# ir_smd.net
KiCad netlist of a schematic drawn in EAGLE
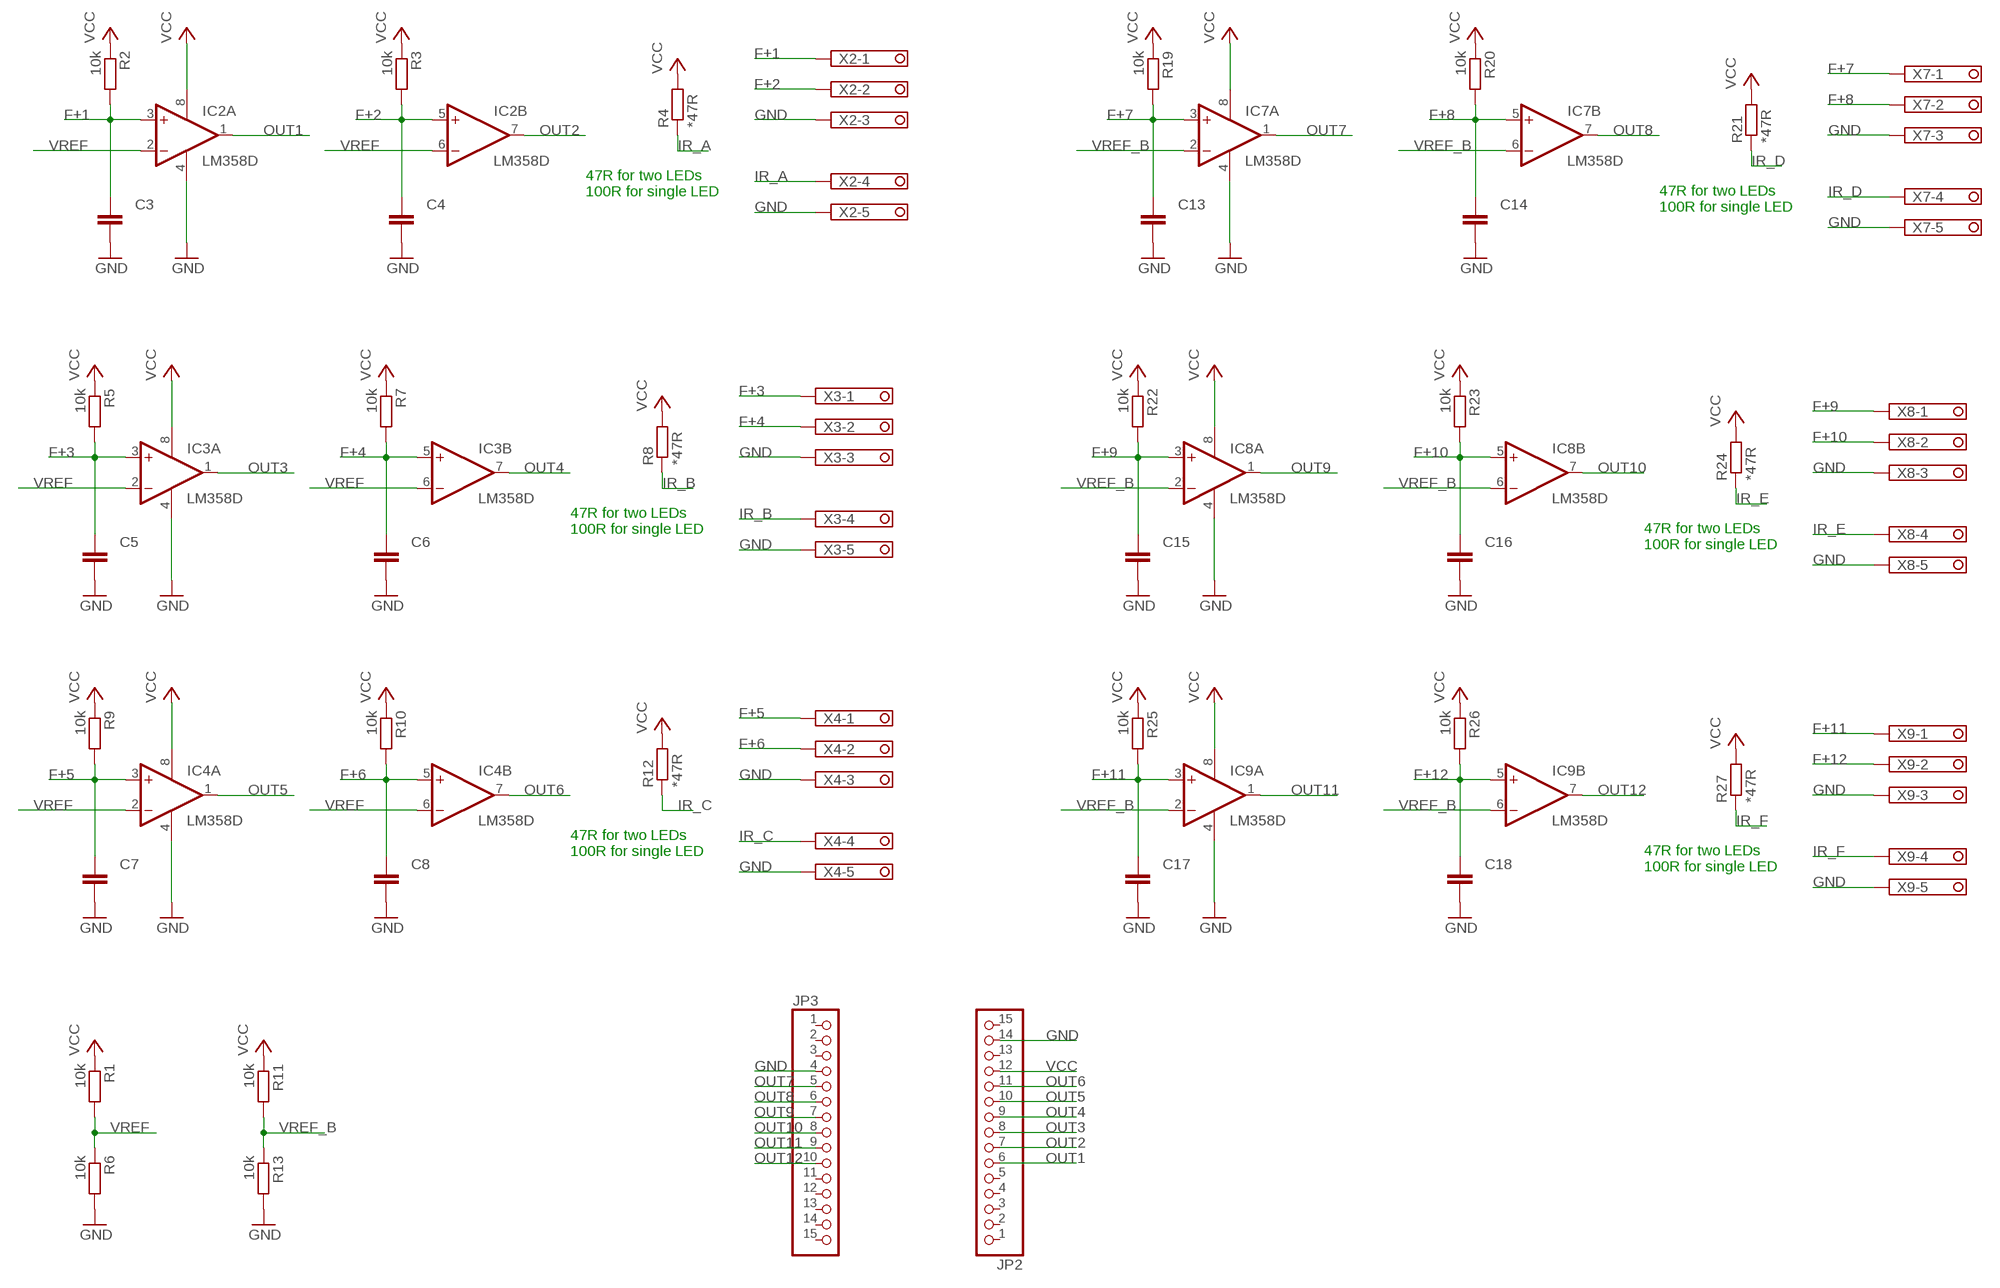
[diagram p0: schematic, sheet 1]

(export (version "E")
  (design (tool "Eeschema 10.0.6"))
  (components
    (comp (ref "C3")
      (value "C-EUC0603")
      (footprint "eagle-import:C0603")
      (libsource (lib "eagle-import") (part "C-EUC0603"))
    )
    (comp (ref "C4")
      (value "C-EUC0603")
      (footprint "eagle-import:C0603")
      (libsource (lib "eagle-import") (part "C-EUC0603"))
    )
    (comp (ref "C5")
      (value "C-EUC0603")
      (footprint "eagle-import:C0603")
      (libsource (lib "eagle-import") (part "C-EUC0603"))
    )
    (comp (ref "C6")
      (value "C-EUC0603")
      (footprint "eagle-import:C0603")
      (libsource (lib "eagle-import") (part "C-EUC0603"))
    )
    (comp (ref "C7")
      (value "C-EUC0603")
      (footprint "eagle-import:C0603")
      (libsource (lib "eagle-import") (part "C-EUC0603"))
    )
    (comp (ref "C8")
      (value "C-EUC0603")
      (footprint "eagle-import:C0603")
      (libsource (lib "eagle-import") (part "C-EUC0603"))
    )
    (comp (ref "C13")
      (value "C-EUC0603")
      (footprint "eagle-import:C0603")
      (libsource (lib "eagle-import") (part "C-EUC0603"))
    )
    (comp (ref "C14")
      (value "C-EUC0603")
      (footprint "eagle-import:C0603")
      (libsource (lib "eagle-import") (part "C-EUC0603"))
    )
    (comp (ref "C15")
      (value "C-EUC0603")
      (footprint "eagle-import:C0603")
      (libsource (lib "eagle-import") (part "C-EUC0603"))
    )
    (comp (ref "C16")
      (value "C-EUC0603")
      (footprint "eagle-import:C0603")
      (libsource (lib "eagle-import") (part "C-EUC0603"))
    )
    (comp (ref "C17")
      (value "C-EUC0603")
      (footprint "eagle-import:C0603")
      (libsource (lib "eagle-import") (part "C-EUC0603"))
    )
    (comp (ref "C18")
      (value "C-EUC0603")
      (footprint "eagle-import:C0603")
      (libsource (lib "eagle-import") (part "C-EUC0603"))
    )
    (comp (ref "IC2")
      (value "LM358D")
      (footprint "eagle-import:SO08")
      (libsource (lib "eagle-import") (part "LM358D"))
    )
    (comp (ref "IC3")
      (value "LM358D")
      (footprint "eagle-import:SO08")
      (libsource (lib "eagle-import") (part "LM358D"))
    )
    (comp (ref "IC4")
      (value "LM358D")
      (footprint "eagle-import:SO08")
      (libsource (lib "eagle-import") (part "LM358D"))
    )
    (comp (ref "IC7")
      (value "LM358D")
      (footprint "eagle-import:SO08")
      (libsource (lib "eagle-import") (part "LM358D"))
    )
    (comp (ref "IC8")
      (value "LM358D")
      (footprint "eagle-import:SO08")
      (libsource (lib "eagle-import") (part "LM358D"))
    )
    (comp (ref "IC9")
      (value "LM358D")
      (footprint "eagle-import:SO08")
      (libsource (lib "eagle-import") (part "LM358D"))
    )
    (comp (ref "JP2")
      (value "PINHD-1X15")
      (footprint "eagle-import:1X15")
      (libsource (lib "eagle-import") (part "PINHD-1X15"))
    )
    (comp (ref "JP3")
      (value "PINHD-1X15")
      (footprint "eagle-import:1X15")
      (libsource (lib "eagle-import") (part "PINHD-1X15"))
    )
    (comp (ref "R1")
      (value "10k")
      (footprint "eagle-import:R0805")
      (libsource (lib "eagle-import") (part "R-EU_R0805"))
    )
    (comp (ref "R2")
      (value "10k")
      (footprint "eagle-import:R0805")
      (libsource (lib "eagle-import") (part "R-EU_R0805"))
    )
    (comp (ref "R3")
      (value "10k")
      (footprint "eagle-import:R0805")
      (libsource (lib "eagle-import") (part "R-EU_R0805"))
    )
    (comp (ref "R4")
      (value "*47R")
      (footprint "eagle-import:R0805")
      (libsource (lib "eagle-import") (part "R-EU_R0805"))
    )
    (comp (ref "R5")
      (value "10k")
      (footprint "eagle-import:R0805")
      (libsource (lib "eagle-import") (part "R-EU_R0805"))
    )
    (comp (ref "R6")
      (value "10k")
      (footprint "eagle-import:R0805")
      (libsource (lib "eagle-import") (part "R-EU_R0805"))
    )
    (comp (ref "R7")
      (value "10k")
      (footprint "eagle-import:R0805")
      (libsource (lib "eagle-import") (part "R-EU_R0805"))
    )
    (comp (ref "R8")
      (value "*47R")
      (footprint "eagle-import:R0805")
      (libsource (lib "eagle-import") (part "R-EU_R0805"))
    )
    (comp (ref "R9")
      (value "10k")
      (footprint "eagle-import:R0805")
      (libsource (lib "eagle-import") (part "R-EU_R0805"))
    )
    (comp (ref "R10")
      (value "10k")
      (footprint "eagle-import:R0805")
      (libsource (lib "eagle-import") (part "R-EU_R0805"))
    )
    (comp (ref "R11")
      (value "10k")
      (footprint "eagle-import:R0805")
      (libsource (lib "eagle-import") (part "R-EU_R0805"))
    )
    (comp (ref "R12")
      (value "*47R")
      (footprint "eagle-import:R0805")
      (libsource (lib "eagle-import") (part "R-EU_R0805"))
    )
    (comp (ref "R13")
      (value "10k")
      (footprint "eagle-import:R0805")
      (libsource (lib "eagle-import") (part "R-EU_R0805"))
    )
    (comp (ref "R19")
      (value "10k")
      (footprint "eagle-import:R0805")
      (libsource (lib "eagle-import") (part "R-EU_R0805"))
    )
    (comp (ref "R20")
      (value "10k")
      (footprint "eagle-import:R0805")
      (libsource (lib "eagle-import") (part "R-EU_R0805"))
    )
    (comp (ref "R21")
      (value "*47R")
      (footprint "eagle-import:R0805")
      (libsource (lib "eagle-import") (part "R-EU_R0805"))
    )
    (comp (ref "R22")
      (value "10k")
      (footprint "eagle-import:R0805")
      (libsource (lib "eagle-import") (part "R-EU_R0805"))
    )
    (comp (ref "R23")
      (value "10k")
      (footprint "eagle-import:R0805")
      (libsource (lib "eagle-import") (part "R-EU_R0805"))
    )
    (comp (ref "R24")
      (value "*47R")
      (footprint "eagle-import:R0805")
      (libsource (lib "eagle-import") (part "R-EU_R0805"))
    )
    (comp (ref "R25")
      (value "10k")
      (footprint "eagle-import:R0805")
      (libsource (lib "eagle-import") (part "R-EU_R0805"))
    )
    (comp (ref "R26")
      (value "10k")
      (footprint "eagle-import:R0805")
      (libsource (lib "eagle-import") (part "R-EU_R0805"))
    )
    (comp (ref "R27")
      (value "*47R")
      (footprint "eagle-import:R0805")
      (libsource (lib "eagle-import") (part "R-EU_R0805"))
    )
    (comp (ref "X2")
      (value "1751277")
      (footprint "eagle-import:1751277")
      (libsource (lib "eagle-import") (part "1751277"))
    )
    (comp (ref "X3")
      (value "1751277")
      (footprint "eagle-import:1751277")
      (libsource (lib "eagle-import") (part "1751277"))
    )
    (comp (ref "X4")
      (value "1751277")
      (footprint "eagle-import:1751277")
      (libsource (lib "eagle-import") (part "1751277"))
    )
    (comp (ref "X7")
      (value "1751277")
      (footprint "eagle-import:1751277")
      (libsource (lib "eagle-import") (part "1751277"))
    )
    (comp (ref "X8")
      (value "1751277")
      (footprint "eagle-import:1751277")
      (libsource (lib "eagle-import") (part "1751277"))
    )
    (comp (ref "X9")
      (value "1751277")
      (footprint "eagle-import:1751277")
      (libsource (lib "eagle-import") (part "1751277"))
    )
  )
  (nets
    (net (code "1") (name "/F+1") (class "Default")
      (node (ref "C3") (pin "1") (pinfunction "1_1") (pintype "passive"))
      (node (ref "IC2") (pin "3") (pinfunction "+IN_3") (pintype "input"))
      (node (ref "R2") (pin "2") (pinfunction "2_2") (pintype "passive"))
      (node (ref "X2") (pin "1") (pinfunction "K_1") (pintype "passive"))
    )
    (net (code "2") (name "/F+2") (class "Default")
      (node (ref "C4") (pin "1") (pinfunction "1_1") (pintype "passive"))
      (node (ref "IC2") (pin "5") (pinfunction "+IN_5") (pintype "input"))
      (node (ref "R3") (pin "2") (pinfunction "2_2") (pintype "passive"))
      (node (ref "X2") (pin "2") (pinfunction "K_2") (pintype "passive"))
    )
    (net (code "3") (name "/F+3") (class "Default")
      (node (ref "C5") (pin "1") (pinfunction "1_1") (pintype "passive"))
      (node (ref "IC3") (pin "3") (pinfunction "+IN_3") (pintype "input"))
      (node (ref "R5") (pin "2") (pinfunction "2_2") (pintype "passive"))
      (node (ref "X3") (pin "1") (pinfunction "K_1") (pintype "passive"))
    )
    (net (code "4") (name "/F+4") (class "Default")
      (node (ref "C6") (pin "1") (pinfunction "1_1") (pintype "passive"))
      (node (ref "IC3") (pin "5") (pinfunction "+IN_5") (pintype "input"))
      (node (ref "R7") (pin "2") (pinfunction "2_2") (pintype "passive"))
      (node (ref "X3") (pin "2") (pinfunction "K_2") (pintype "passive"))
    )
    (net (code "5") (name "/F+5") (class "Default")
      (node (ref "C7") (pin "1") (pinfunction "1_1") (pintype "passive"))
      (node (ref "IC4") (pin "3") (pinfunction "+IN_3") (pintype "input"))
      (node (ref "R9") (pin "2") (pinfunction "2_2") (pintype "passive"))
      (node (ref "X4") (pin "1") (pinfunction "K_1") (pintype "passive"))
    )
    (net (code "6") (name "/F+6") (class "Default")
      (node (ref "C8") (pin "1") (pinfunction "1_1") (pintype "passive"))
      (node (ref "IC4") (pin "5") (pinfunction "+IN_5") (pintype "input"))
      (node (ref "R10") (pin "2") (pinfunction "2_2") (pintype "passive"))
      (node (ref "X4") (pin "2") (pinfunction "K_2") (pintype "passive"))
    )
    (net (code "7") (name "/F+7") (class "Default")
      (node (ref "C13") (pin "1") (pinfunction "1_1") (pintype "passive"))
      (node (ref "IC7") (pin "3") (pinfunction "+IN_3") (pintype "input"))
      (node (ref "R19") (pin "2") (pinfunction "2_2") (pintype "passive"))
      (node (ref "X7") (pin "1") (pinfunction "K_1") (pintype "passive"))
    )
    (net (code "8") (name "/F+8") (class "Default")
      (node (ref "C14") (pin "1") (pinfunction "1_1") (pintype "passive"))
      (node (ref "IC7") (pin "5") (pinfunction "+IN_5") (pintype "input"))
      (node (ref "R20") (pin "2") (pinfunction "2_2") (pintype "passive"))
      (node (ref "X7") (pin "2") (pinfunction "K_2") (pintype "passive"))
    )
    (net (code "9") (name "/F+9") (class "Default")
      (node (ref "C15") (pin "1") (pinfunction "1_1") (pintype "passive"))
      (node (ref "IC8") (pin "3") (pinfunction "+IN_3") (pintype "input"))
      (node (ref "R22") (pin "2") (pinfunction "2_2") (pintype "passive"))
      (node (ref "X8") (pin "1") (pinfunction "K_1") (pintype "passive"))
    )
    (net (code "10") (name "/F+10") (class "Default")
      (node (ref "C16") (pin "1") (pinfunction "1_1") (pintype "passive"))
      (node (ref "IC8") (pin "5") (pinfunction "+IN_5") (pintype "input"))
      (node (ref "R23") (pin "2") (pinfunction "2_2") (pintype "passive"))
      (node (ref "X8") (pin "2") (pinfunction "K_2") (pintype "passive"))
    )
    (net (code "11") (name "/F+11") (class "Default")
      (node (ref "C17") (pin "1") (pinfunction "1_1") (pintype "passive"))
      (node (ref "IC9") (pin "3") (pinfunction "+IN_3") (pintype "input"))
      (node (ref "R25") (pin "2") (pinfunction "2_2") (pintype "passive"))
      (node (ref "X9") (pin "1") (pinfunction "K_1") (pintype "passive"))
    )
    (net (code "12") (name "/F+12") (class "Default")
      (node (ref "C18") (pin "1") (pinfunction "1_1") (pintype "passive"))
      (node (ref "IC9") (pin "5") (pinfunction "+IN_5") (pintype "input"))
      (node (ref "R26") (pin "2") (pinfunction "2_2") (pintype "passive"))
      (node (ref "X9") (pin "2") (pinfunction "K_2") (pintype "passive"))
    )
    (net (code "13") (name "/IR_A") (class "Default")
      (node (ref "R4") (pin "1") (pinfunction "1_1") (pintype "passive"))
      (node (ref "X2") (pin "4") (pinfunction "K_4") (pintype "passive"))
    )
    (net (code "14") (name "/IR_B") (class "Default")
      (node (ref "R8") (pin "1") (pinfunction "1_1") (pintype "passive"))
      (node (ref "X3") (pin "4") (pinfunction "K_4") (pintype "passive"))
    )
    (net (code "15") (name "/IR_C") (class "Default")
      (node (ref "R12") (pin "1") (pinfunction "1_1") (pintype "passive"))
      (node (ref "X4") (pin "4") (pinfunction "K_4") (pintype "passive"))
    )
    (net (code "16") (name "/IR_D") (class "Default")
      (node (ref "R21") (pin "1") (pinfunction "1_1") (pintype "passive"))
      (node (ref "X7") (pin "4") (pinfunction "K_4") (pintype "passive"))
    )
    (net (code "17") (name "/IR_E") (class "Default")
      (node (ref "R24") (pin "1") (pinfunction "1_1") (pintype "passive"))
      (node (ref "X8") (pin "4") (pinfunction "K_4") (pintype "passive"))
    )
    (net (code "18") (name "/IR_F") (class "Default")
      (node (ref "R27") (pin "1") (pinfunction "1_1") (pintype "passive"))
      (node (ref "X9") (pin "4") (pinfunction "K_4") (pintype "passive"))
    )
    (net (code "19") (name "/OUT1") (class "Default")
      (node (ref "IC2") (pin "1") (pinfunction "OUT_1") (pintype "output"))
      (node (ref "JP2") (pin "6") (pinfunction "6_6") (pintype "passive"))
    )
    (net (code "20") (name "/OUT2") (class "Default")
      (node (ref "IC2") (pin "7") (pinfunction "OUT_7") (pintype "output"))
      (node (ref "JP2") (pin "7") (pinfunction "7_7") (pintype "passive"))
    )
    (net (code "21") (name "/OUT3") (class "Default")
      (node (ref "IC3") (pin "1") (pinfunction "OUT_1") (pintype "output"))
      (node (ref "JP2") (pin "8") (pinfunction "8_8") (pintype "passive"))
    )
    (net (code "22") (name "/OUT4") (class "Default")
      (node (ref "IC3") (pin "7") (pinfunction "OUT_7") (pintype "output"))
      (node (ref "JP2") (pin "9") (pinfunction "9_9") (pintype "passive"))
    )
    (net (code "23") (name "/OUT5") (class "Default")
      (node (ref "IC4") (pin "1") (pinfunction "OUT_1") (pintype "output"))
      (node (ref "JP2") (pin "10") (pinfunction "10_10") (pintype "passive"))
    )
    (net (code "24") (name "/OUT6") (class "Default")
      (node (ref "IC4") (pin "7") (pinfunction "OUT_7") (pintype "output"))
      (node (ref "JP2") (pin "11") (pinfunction "11_11") (pintype "passive"))
    )
    (net (code "25") (name "/OUT7") (class "Default")
      (node (ref "IC7") (pin "1") (pinfunction "OUT_1") (pintype "output"))
      (node (ref "JP3") (pin "5") (pinfunction "5_5") (pintype "passive"))
    )
    (net (code "26") (name "/OUT8") (class "Default")
      (node (ref "IC7") (pin "7") (pinfunction "OUT_7") (pintype "output"))
      (node (ref "JP3") (pin "6") (pinfunction "6_6") (pintype "passive"))
    )
    (net (code "27") (name "/OUT9") (class "Default")
      (node (ref "IC8") (pin "1") (pinfunction "OUT_1") (pintype "output"))
      (node (ref "JP3") (pin "7") (pinfunction "7_7") (pintype "passive"))
    )
    (net (code "28") (name "/OUT10") (class "Default")
      (node (ref "IC8") (pin "7") (pinfunction "OUT_7") (pintype "output"))
      (node (ref "JP3") (pin "8") (pinfunction "8_8") (pintype "passive"))
    )
    (net (code "29") (name "/OUT11") (class "Default")
      (node (ref "IC9") (pin "1") (pinfunction "OUT_1") (pintype "output"))
      (node (ref "JP3") (pin "9") (pinfunction "9_9") (pintype "passive"))
    )
    (net (code "30") (name "/OUT12") (class "Default")
      (node (ref "IC9") (pin "7") (pinfunction "OUT_7") (pintype "output"))
      (node (ref "JP3") (pin "10") (pinfunction "10_10") (pintype "passive"))
    )
    (net (code "31") (name "/VREF") (class "Default")
      (node (ref "IC2") (pin "2") (pinfunction "-IN_2") (pintype "input"))
      (node (ref "IC2") (pin "6") (pinfunction "-IN_6") (pintype "input"))
      (node (ref "IC3") (pin "2") (pinfunction "-IN_2") (pintype "input"))
      (node (ref "IC3") (pin "6") (pinfunction "-IN_6") (pintype "input"))
      (node (ref "IC4") (pin "2") (pinfunction "-IN_2") (pintype "input"))
      (node (ref "IC4") (pin "6") (pinfunction "-IN_6") (pintype "input"))
      (node (ref "R1") (pin "2") (pinfunction "2_2") (pintype "passive"))
      (node (ref "R6") (pin "1") (pinfunction "1_1") (pintype "passive"))
    )
    (net (code "32") (name "/VREF_B") (class "Default")
      (node (ref "IC7") (pin "2") (pinfunction "-IN_2") (pintype "input"))
      (node (ref "IC7") (pin "6") (pinfunction "-IN_6") (pintype "input"))
      (node (ref "IC8") (pin "2") (pinfunction "-IN_2") (pintype "input"))
      (node (ref "IC8") (pin "6") (pinfunction "-IN_6") (pintype "input"))
      (node (ref "IC9") (pin "2") (pinfunction "-IN_2") (pintype "input"))
      (node (ref "IC9") (pin "6") (pinfunction "-IN_6") (pintype "input"))
      (node (ref "R11") (pin "2") (pinfunction "2_2") (pintype "passive"))
      (node (ref "R13") (pin "1") (pinfunction "1_1") (pintype "passive"))
    )
    (net (code "33") (name "GND") (class "Default")
      (node (ref "C13") (pin "2") (pinfunction "2_2") (pintype "passive"))
      (node (ref "C14") (pin "2") (pinfunction "2_2") (pintype "passive"))
      (node (ref "C15") (pin "2") (pinfunction "2_2") (pintype "passive"))
      (node (ref "C16") (pin "2") (pinfunction "2_2") (pintype "passive"))
      (node (ref "C17") (pin "2") (pinfunction "2_2") (pintype "passive"))
      (node (ref "C18") (pin "2") (pinfunction "2_2") (pintype "passive"))
      (node (ref "C3") (pin "2") (pinfunction "2_2") (pintype "passive"))
      (node (ref "C4") (pin "2") (pinfunction "2_2") (pintype "passive"))
      (node (ref "C5") (pin "2") (pinfunction "2_2") (pintype "passive"))
      (node (ref "C6") (pin "2") (pinfunction "2_2") (pintype "passive"))
      (node (ref "C7") (pin "2") (pinfunction "2_2") (pintype "passive"))
      (node (ref "C8") (pin "2") (pinfunction "2_2") (pintype "passive"))
      (node (ref "IC2") (pin "4") (pinfunction "V-_4") (pintype "power_in"))
      (node (ref "IC3") (pin "4") (pinfunction "V-_4") (pintype "power_in"))
      (node (ref "IC4") (pin "4") (pinfunction "V-_4") (pintype "power_in"))
      (node (ref "IC7") (pin "4") (pinfunction "V-_4") (pintype "power_in"))
      (node (ref "IC8") (pin "4") (pinfunction "V-_4") (pintype "power_in"))
      (node (ref "IC9") (pin "4") (pinfunction "V-_4") (pintype "power_in"))
      (node (ref "JP2") (pin "14") (pinfunction "14_14") (pintype "passive"))
      (node (ref "JP3") (pin "4") (pinfunction "4_4") (pintype "passive"))
      (node (ref "R13") (pin "2") (pinfunction "2_2") (pintype "passive"))
      (node (ref "R6") (pin "2") (pinfunction "2_2") (pintype "passive"))
      (node (ref "X2") (pin "3") (pinfunction "K_3") (pintype "passive"))
      (node (ref "X2") (pin "5") (pinfunction "K_5") (pintype "passive"))
      (node (ref "X3") (pin "3") (pinfunction "K_3") (pintype "passive"))
      (node (ref "X3") (pin "5") (pinfunction "K_5") (pintype "passive"))
      (node (ref "X4") (pin "3") (pinfunction "K_3") (pintype "passive"))
      (node (ref "X4") (pin "5") (pinfunction "K_5") (pintype "passive"))
      (node (ref "X7") (pin "3") (pinfunction "K_3") (pintype "passive"))
      (node (ref "X7") (pin "5") (pinfunction "K_5") (pintype "passive"))
      (node (ref "X8") (pin "3") (pinfunction "K_3") (pintype "passive"))
      (node (ref "X8") (pin "5") (pinfunction "K_5") (pintype "passive"))
      (node (ref "X9") (pin "3") (pinfunction "K_3") (pintype "passive"))
      (node (ref "X9") (pin "5") (pinfunction "K_5") (pintype "passive"))
    )
    (net (code "34") (name "VCC") (class "Default")
      (node (ref "IC2") (pin "8") (pinfunction "V+_8") (pintype "power_in"))
      (node (ref "IC3") (pin "8") (pinfunction "V+_8") (pintype "power_in"))
      (node (ref "IC4") (pin "8") (pinfunction "V+_8") (pintype "power_in"))
      (node (ref "IC7") (pin "8") (pinfunction "V+_8") (pintype "power_in"))
      (node (ref "IC8") (pin "8") (pinfunction "V+_8") (pintype "power_in"))
      (node (ref "IC9") (pin "8") (pinfunction "V+_8") (pintype "power_in"))
      (node (ref "JP2") (pin "12") (pinfunction "12_12") (pintype "passive"))
      (node (ref "R1") (pin "1") (pinfunction "1_1") (pintype "passive"))
      (node (ref "R10") (pin "1") (pinfunction "1_1") (pintype "passive"))
      (node (ref "R11") (pin "1") (pinfunction "1_1") (pintype "passive"))
      (node (ref "R12") (pin "2") (pinfunction "2_2") (pintype "passive"))
      (node (ref "R19") (pin "1") (pinfunction "1_1") (pintype "passive"))
      (node (ref "R2") (pin "1") (pinfunction "1_1") (pintype "passive"))
      (node (ref "R20") (pin "1") (pinfunction "1_1") (pintype "passive"))
      (node (ref "R21") (pin "2") (pinfunction "2_2") (pintype "passive"))
      (node (ref "R22") (pin "1") (pinfunction "1_1") (pintype "passive"))
      (node (ref "R23") (pin "1") (pinfunction "1_1") (pintype "passive"))
      (node (ref "R24") (pin "2") (pinfunction "2_2") (pintype "passive"))
      (node (ref "R25") (pin "1") (pinfunction "1_1") (pintype "passive"))
      (node (ref "R26") (pin "1") (pinfunction "1_1") (pintype "passive"))
      (node (ref "R27") (pin "2") (pinfunction "2_2") (pintype "passive"))
      (node (ref "R3") (pin "1") (pinfunction "1_1") (pintype "passive"))
      (node (ref "R4") (pin "2") (pinfunction "2_2") (pintype "passive"))
      (node (ref "R5") (pin "1") (pinfunction "1_1") (pintype "passive"))
      (node (ref "R7") (pin "1") (pinfunction "1_1") (pintype "passive"))
      (node (ref "R8") (pin "2") (pinfunction "2_2") (pintype "passive"))
      (node (ref "R9") (pin "1") (pinfunction "1_1") (pintype "passive"))
    )
    (net (code "35") (name "unconnected-(JP2-Pad1)") (class "Default")
      (node (ref "JP2") (pin "1") (pinfunction "1_1") (pintype "passive"))
    )
    (net (code "36") (name "unconnected-(JP2-Pad2)") (class "Default")
      (node (ref "JP2") (pin "2") (pinfunction "2_2") (pintype "passive"))
    )
    (net (code "37") (name "unconnected-(JP2-Pad3)") (class "Default")
      (node (ref "JP2") (pin "3") (pinfunction "3_3") (pintype "passive"))
    )
    (net (code "38") (name "unconnected-(JP2-Pad4)") (class "Default")
      (node (ref "JP2") (pin "4") (pinfunction "4_4") (pintype "passive"))
    )
    (net (code "39") (name "unconnected-(JP2-Pad5)") (class "Default")
      (node (ref "JP2") (pin "5") (pinfunction "5_5") (pintype "passive"))
    )
    (net (code "40") (name "unconnected-(JP2-Pad13)") (class "Default")
      (node (ref "JP2") (pin "13") (pinfunction "13_13") (pintype "passive"))
    )
    (net (code "41") (name "unconnected-(JP2-Pad15)") (class "Default")
      (node (ref "JP2") (pin "15") (pinfunction "15_15") (pintype "passive"))
    )
    (net (code "42") (name "unconnected-(JP3-Pad1)") (class "Default")
      (node (ref "JP3") (pin "1") (pinfunction "1_1") (pintype "passive"))
    )
    (net (code "43") (name "unconnected-(JP3-Pad2)") (class "Default")
      (node (ref "JP3") (pin "2") (pinfunction "2_2") (pintype "passive"))
    )
    (net (code "44") (name "unconnected-(JP3-Pad3)") (class "Default")
      (node (ref "JP3") (pin "3") (pinfunction "3_3") (pintype "passive"))
    )
    (net (code "45") (name "unconnected-(JP3-Pad11)") (class "Default")
      (node (ref "JP3") (pin "11") (pinfunction "11_11") (pintype "passive"))
    )
    (net (code "46") (name "unconnected-(JP3-Pad12)") (class "Default")
      (node (ref "JP3") (pin "12") (pinfunction "12_12") (pintype "passive"))
    )
    (net (code "47") (name "unconnected-(JP3-Pad13)") (class "Default")
      (node (ref "JP3") (pin "13") (pinfunction "13_13") (pintype "passive"))
    )
    (net (code "48") (name "unconnected-(JP3-Pad14)") (class "Default")
      (node (ref "JP3") (pin "14") (pinfunction "14_14") (pintype "passive"))
    )
    (net (code "49") (name "unconnected-(JP3-Pad15)") (class "Default")
      (node (ref "JP3") (pin "15") (pinfunction "15_15") (pintype "passive"))
    )
  )
)
